# wemos_rfmaster.net
KiCad netlist of a schematic drawn in EAGLE
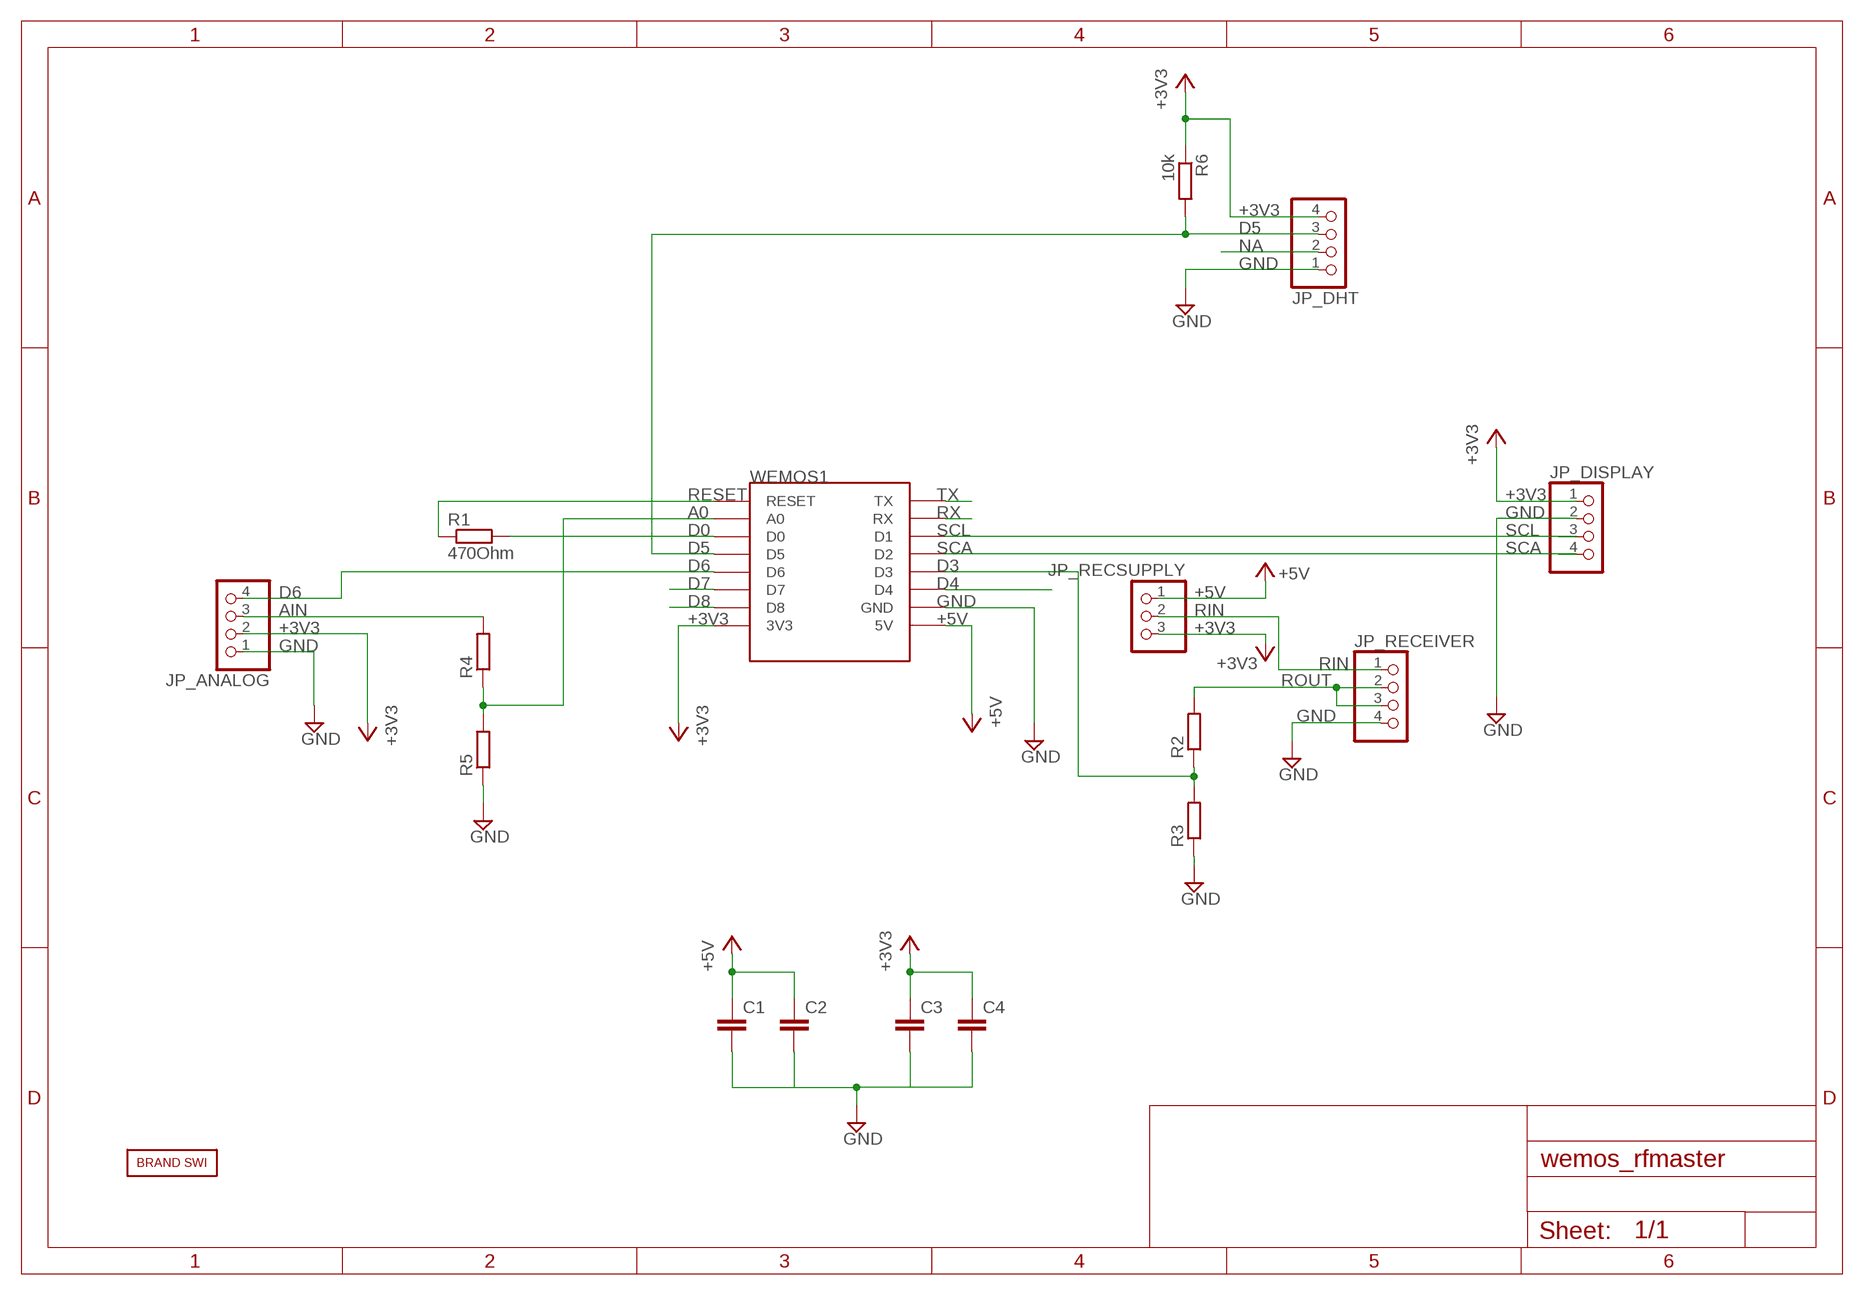
[diagram p0: schematic, sheet 1]

(export (version "E")
  (design (tool "Eeschema 10.0.6"))
  (components
    (comp (ref "C1")
      (value "C-EUC1210")
      (footprint "eagle-import:C1210")
      (libsource (lib "eagle-import") (part "C-EUC1210"))
    )
    (comp (ref "C2")
      (value "C-EUC1210")
      (footprint "eagle-import:C1210")
      (libsource (lib "eagle-import") (part "C-EUC1210"))
    )
    (comp (ref "C3")
      (value "C-EUC1210")
      (footprint "eagle-import:C1210")
      (libsource (lib "eagle-import") (part "C-EUC1210"))
    )
    (comp (ref "C4")
      (value "C-EUC1210")
      (footprint "eagle-import:C1210")
      (libsource (lib "eagle-import") (part "C-EUC1210"))
    )
    (comp (ref "JP_ANALOG")
      (value "PINHD-1X4")
      (footprint "eagle-import:1X04")
      (libsource (lib "eagle-import") (part "PINHD-1X4"))
    )
    (comp (ref "JP_DHT")
      (value "PINHD-1X4")
      (footprint "eagle-import:1X04")
      (libsource (lib "eagle-import") (part "pinhead_325_PINHD-1X4"))
    )
    (comp (ref "JP_DISPLAY")
      (value "PINHD-1X4")
      (footprint "eagle-import:1X04")
      (libsource (lib "eagle-import") (part "PINHD-1X4"))
    )
    (comp (ref "JP_RECEIVER")
      (value "PINHD-1X4")
      (footprint "eagle-import:1X04")
      (libsource (lib "eagle-import") (part "PINHD-1X4"))
    )
    (comp (ref "JP_RECSUPPLY")
      (value "PINHD-1X3")
      (footprint "eagle-import:1X03")
      (libsource (lib "eagle-import") (part "PINHD-1X3"))
    )
    (comp (ref "R1")
      (value "470Ohm")
      (footprint "eagle-import:R0805")
      (libsource (lib "eagle-import") (part "R-EU_R0805"))
    )
    (comp (ref "R2")
      (value "R-EU_R0805")
      (footprint "eagle-import:R0805")
      (libsource (lib "eagle-import") (part "R-EU_R0805"))
    )
    (comp (ref "R3")
      (value "R-EU_R0805")
      (footprint "eagle-import:R0805")
      (libsource (lib "eagle-import") (part "R-EU_R0805"))
    )
    (comp (ref "R4")
      (value "R-EU_R0805")
      (footprint "eagle-import:R0805")
      (libsource (lib "eagle-import") (part "R-EU_R0805"))
    )
    (comp (ref "R5")
      (value "R-EU_R0805")
      (footprint "eagle-import:R0805")
      (libsource (lib "eagle-import") (part "R-EU_R0805"))
    )
    (comp (ref "R6")
      (value "10k")
      (footprint "eagle-import:R0805")
      (libsource (lib "eagle-import") (part "R-EU_R0805"))
    )
    (comp (ref "U$2")
      (value "BRAND_SWI5X7")
      (footprint "eagle-import:BRAND_SWI_5X7")
      (libsource (lib "eagle-import") (part "BRAND_SWI5X7"))
    )
    (comp (ref "WEMOS1")
      (value "WEMOS-D1-MINI")
      (footprint "eagle-import:WEMOS-D1-MINI")
      (libsource (lib "eagle-import") (part "WEMOS-D1-MINI"))
    )
  )
  (nets
    (net (code "1") (name "+3V3") (class "Default")
      (node (ref "C3") (pin "1") (pinfunction "1_1") (pintype "passive"))
      (node (ref "C4") (pin "1") (pinfunction "1_1") (pintype "passive"))
      (node (ref "JP_ANALOG") (pin "2") (pinfunction "2_2") (pintype "passive"))
      (node (ref "JP_DHT") (pin "4") (pinfunction "4_4") (pintype "passive"))
      (node (ref "JP_DISPLAY") (pin "1") (pinfunction "1_1") (pintype "passive"))
      (node (ref "JP_RECSUPPLY") (pin "3") (pinfunction "3_3") (pintype "passive"))
      (node (ref "R6") (pin "1") (pinfunction "1_1") (pintype "passive"))
      (node (ref "WEMOS1") (pin "3V3") (pinfunction "3V3_3V3") (pintype "bidirectional"))
    )
    (net (code "2") (name "+5V") (class "Default")
      (node (ref "C1") (pin "1") (pinfunction "1_1") (pintype "passive"))
      (node (ref "C2") (pin "1") (pinfunction "1_1") (pintype "passive"))
      (node (ref "JP_RECSUPPLY") (pin "1") (pinfunction "1_1") (pintype "passive"))
      (node (ref "WEMOS1") (pin "5V") (pinfunction "5V_5V") (pintype "bidirectional"))
    )
    (net (code "3") (name "/A0") (class "Default")
      (node (ref "R4") (pin "1") (pinfunction "1_1") (pintype "passive"))
      (node (ref "R5") (pin "2") (pinfunction "2_2") (pintype "passive"))
      (node (ref "WEMOS1") (pin "A0") (pinfunction "A0_A0") (pintype "bidirectional"))
    )
    (net (code "4") (name "/AIN") (class "Default")
      (node (ref "JP_ANALOG") (pin "3") (pinfunction "3_3") (pintype "passive"))
      (node (ref "R4") (pin "2") (pinfunction "2_2") (pintype "passive"))
    )
    (net (code "5") (name "/D0") (class "Default")
      (node (ref "R1") (pin "2") (pinfunction "2_2") (pintype "passive"))
      (node (ref "WEMOS1") (pin "D0") (pinfunction "D0_D0") (pintype "bidirectional"))
    )
    (net (code "6") (name "/D3") (class "Default")
      (node (ref "R2") (pin "1") (pinfunction "1_1") (pintype "passive"))
      (node (ref "R3") (pin "2") (pinfunction "2_2") (pintype "passive"))
      (node (ref "WEMOS1") (pin "D3") (pinfunction "D3_D3") (pintype "bidirectional"))
    )
    (net (code "7") (name "/D4") (class "Default")
      (node (ref "WEMOS1") (pin "D4") (pinfunction "D4_D4") (pintype "bidirectional"))
    )
    (net (code "8") (name "/D5") (class "Default")
      (node (ref "JP_DHT") (pin "3") (pinfunction "3_3") (pintype "passive"))
      (node (ref "R6") (pin "2") (pinfunction "2_2") (pintype "passive"))
      (node (ref "WEMOS1") (pin "D5") (pinfunction "D5_D5") (pintype "bidirectional"))
    )
    (net (code "9") (name "/D6") (class "Default")
      (node (ref "JP_ANALOG") (pin "4") (pinfunction "4_4") (pintype "passive"))
      (node (ref "WEMOS1") (pin "D6") (pinfunction "D6_D6") (pintype "bidirectional"))
    )
    (net (code "10") (name "/D7") (class "Default")
      (node (ref "WEMOS1") (pin "D7") (pinfunction "D7_D7") (pintype "bidirectional"))
    )
    (net (code "11") (name "/D8") (class "Default")
      (node (ref "WEMOS1") (pin "D8") (pinfunction "D8_D8") (pintype "bidirectional"))
    )
    (net (code "12") (name "/NA") (class "Default")
      (node (ref "JP_DHT") (pin "2") (pinfunction "2_2") (pintype "passive"))
    )
    (net (code "13") (name "/RESET") (class "Default")
      (node (ref "R1") (pin "1") (pinfunction "1_1") (pintype "passive"))
      (node (ref "WEMOS1") (pin "RESET") (pinfunction "RESET_RESET") (pintype "bidirectional"))
    )
    (net (code "14") (name "/RIN") (class "Default")
      (node (ref "JP_RECEIVER") (pin "1") (pinfunction "1_1") (pintype "passive"))
      (node (ref "JP_RECSUPPLY") (pin "2") (pinfunction "2_2") (pintype "passive"))
    )
    (net (code "15") (name "/ROUT") (class "Default")
      (node (ref "JP_RECEIVER") (pin "2") (pinfunction "2_2") (pintype "passive"))
      (node (ref "JP_RECEIVER") (pin "3") (pinfunction "3_3") (pintype "passive"))
      (node (ref "R2") (pin "2") (pinfunction "2_2") (pintype "passive"))
    )
    (net (code "16") (name "/RX") (class "Default")
      (node (ref "WEMOS1") (pin "RX") (pinfunction "RX_RX") (pintype "bidirectional"))
    )
    (net (code "17") (name "/SCA") (class "Default")
      (node (ref "JP_DISPLAY") (pin "4") (pinfunction "4_4") (pintype "passive"))
      (node (ref "WEMOS1") (pin "D2") (pinfunction "D2_D2") (pintype "bidirectional"))
    )
    (net (code "18") (name "/SCL") (class "Default")
      (node (ref "JP_DISPLAY") (pin "3") (pinfunction "3_3") (pintype "passive"))
      (node (ref "WEMOS1") (pin "D1") (pinfunction "D1_D1") (pintype "bidirectional"))
    )
    (net (code "19") (name "/TX") (class "Default")
      (node (ref "WEMOS1") (pin "TX") (pinfunction "TX_TX") (pintype "bidirectional"))
    )
    (net (code "20") (name "GND") (class "Default")
      (node (ref "C1") (pin "2") (pinfunction "2_2") (pintype "passive"))
      (node (ref "C2") (pin "2") (pinfunction "2_2") (pintype "passive"))
      (node (ref "C3") (pin "2") (pinfunction "2_2") (pintype "passive"))
      (node (ref "C4") (pin "2") (pinfunction "2_2") (pintype "passive"))
      (node (ref "JP_ANALOG") (pin "1") (pinfunction "1_1") (pintype "passive"))
      (node (ref "JP_DHT") (pin "1") (pinfunction "1_1") (pintype "passive"))
      (node (ref "JP_DISPLAY") (pin "2") (pinfunction "2_2") (pintype "passive"))
      (node (ref "JP_RECEIVER") (pin "4") (pinfunction "4_4") (pintype "passive"))
      (node (ref "R3") (pin "1") (pinfunction "1_1") (pintype "passive"))
      (node (ref "R5") (pin "1") (pinfunction "1_1") (pintype "passive"))
      (node (ref "WEMOS1") (pin "GND") (pinfunction "GND_GND") (pintype "bidirectional"))
    )
  )
)
